# control_circuit.net
KiCad netlist of a schematic drawn in EAGLE
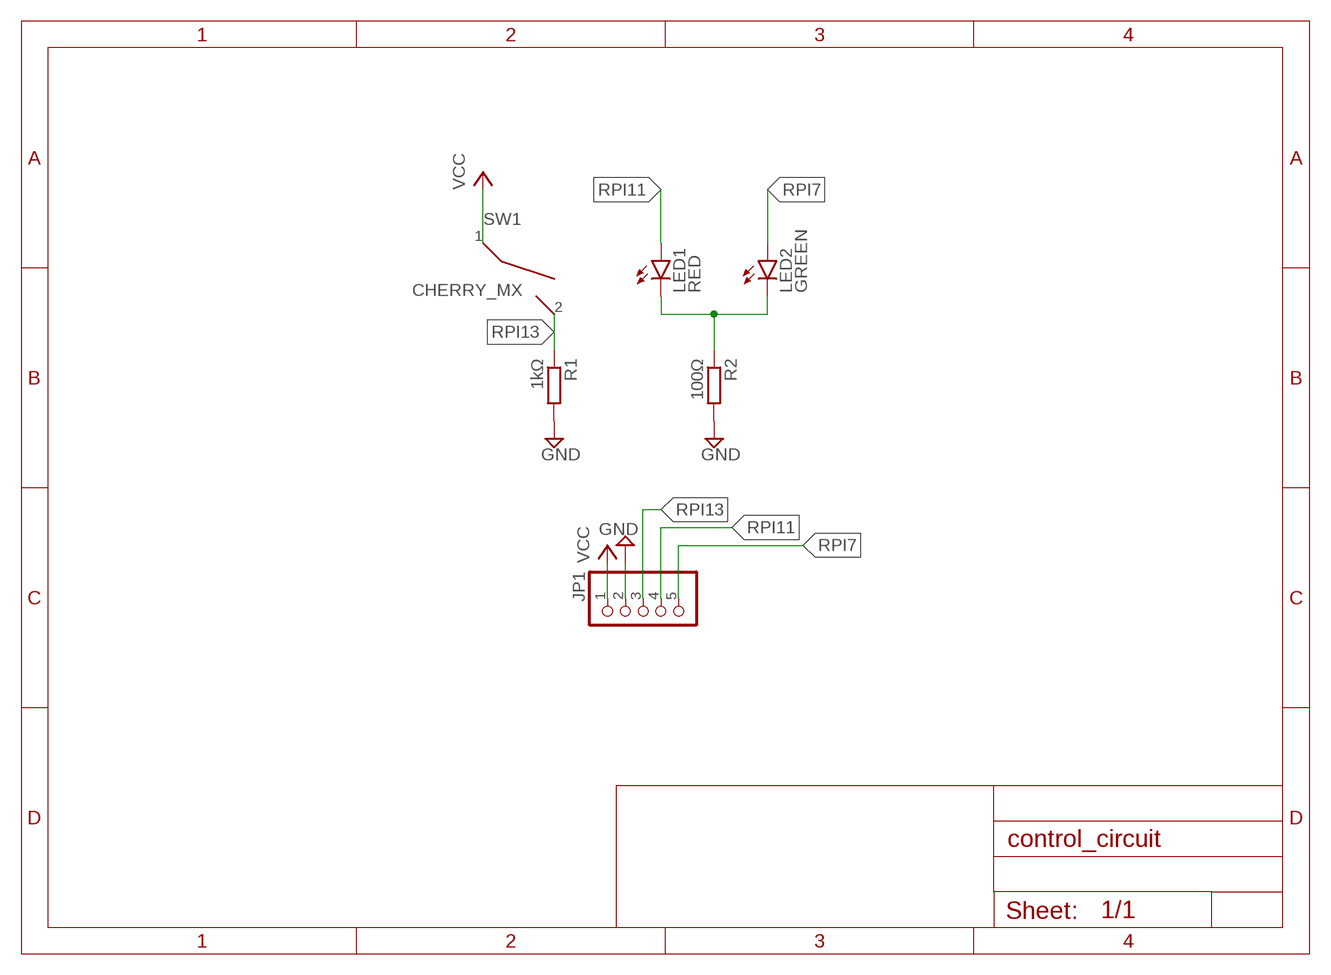
[diagram p0: schematic, sheet 1]

(export (version "E")
  (design (tool "Eeschema 10.0.6"))
  (components
    (comp (ref "JP1")
      (value "PINHD-1X5")
      (footprint "eagle-import:1X05")
      (libsource (lib "eagle-import") (part "PINHD-1X5"))
    )
    (comp (ref "LED1")
      (value "RED")
      (footprint "eagle-import:LED5MM")
      (libsource (lib "eagle-import") (part "LED5MM"))
    )
    (comp (ref "LED2")
      (value "GREEN")
      (footprint "eagle-import:LED5MM")
      (libsource (lib "eagle-import") (part "LED5MM"))
    )
    (comp (ref "R1")
      (value "1kΩ")
      (footprint "eagle-import:0207_10")
      (libsource (lib "eagle-import") (part "R-EU_0207/10"))
    )
    (comp (ref "R2")
      (value "100Ω")
      (footprint "eagle-import:0207_10")
      (libsource (lib "eagle-import") (part "R-EU_0207/10"))
    )
    (comp (ref "SW1")
      (value "CHERRY_MX")
      (footprint "eagle-import:MX1A-XXNN")
      (libsource (lib "eagle-import") (part "CHERRY_MX"))
    )
  )
  (nets
    (net (code "1") (name "GND") (class "Default")
      (node (ref "JP1") (pin "2") (pinfunction "2_2") (pintype "passive"))
      (node (ref "R1") (pin "2") (pinfunction "2_2") (pintype "passive"))
      (node (ref "R2") (pin "2") (pinfunction "2_2") (pintype "passive"))
    )
    (net (code "2") (name "Net-(LED1-C)") (class "Default")
      (node (ref "LED1") (pin "K") (pinfunction "C_K") (pintype "passive"))
      (node (ref "LED2") (pin "K") (pinfunction "C_K") (pintype "passive"))
      (node (ref "R2") (pin "1") (pinfunction "1_1") (pintype "passive"))
    )
    (net (code "3") (name "RPI7") (class "Default")
      (node (ref "JP1") (pin "5") (pinfunction "5_5") (pintype "passive"))
      (node (ref "LED2") (pin "A") (pinfunction "A_A") (pintype "passive"))
    )
    (net (code "4") (name "RPI11") (class "Default")
      (node (ref "JP1") (pin "4") (pinfunction "4_4") (pintype "passive"))
      (node (ref "LED1") (pin "A") (pinfunction "A_A") (pintype "passive"))
    )
    (net (code "5") (name "RPI13") (class "Default")
      (node (ref "JP1") (pin "3") (pinfunction "3_3") (pintype "passive"))
      (node (ref "R1") (pin "1") (pinfunction "1_1") (pintype "passive"))
      (node (ref "SW1") (pin "2") (pinfunction "2_2") (pintype "passive"))
    )
    (net (code "6") (name "VCC") (class "Default")
      (node (ref "JP1") (pin "1") (pinfunction "1_1") (pintype "passive"))
      (node (ref "SW1") (pin "1") (pinfunction "1_1") (pintype "passive"))
    )
  )
)
